# DSO_Front.net
KiCad netlist of a schematic drawn in Altium Designer
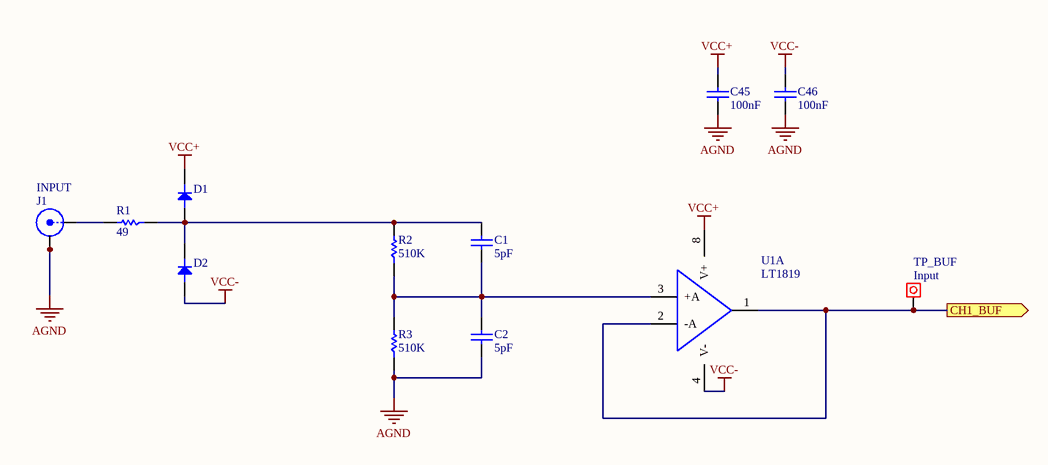
[diagram p0: DSO_Front.SchDoc]

(export (version "E")
  (design (tool "Eeschema 10.0.6"))
  (components
    (comp (ref "C1")
      (value "5pF")
      (footprint "0805C")
      (description "Capacitor")
      (fields (field (name "REVIEWED BY") "RM - 2018/08/05"))
      (libsource (lib "DSO") (part "C"))
    )
    (comp (ref "C2")
      (value "5pF")
      (footprint "0805C")
      (description "Capacitor")
      (fields (field (name "REVIEWED BY") "RM - 2018/08/05"))
      (libsource (lib "DSO") (part "C"))
    )
    (comp (ref "C45")
      (value "100nF")
      (footprint "0805C")
      (description "Capacitor")
      (fields (field (name "REVIEWED BY") "RM - 2018/08/05"))
      (libsource (lib "DSO") (part "C"))
    )
    (comp (ref "C46")
      (value "100nF")
      (footprint "0805C")
      (description "Capacitor")
      (fields (field (name "REVIEWED BY") "RM - 2018/08/05"))
      (libsource (lib "DSO") (part "C"))
    )
    (comp (ref "D1")
      (value "Diode")
      (footprint "SOD-123")
      (fields (field (name "REVIEWED BY") "RM - 2018/08/05"))
      (libsource (lib "DSO") (part "D"))
    )
    (comp (ref "D2")
      (value "Diode")
      (footprint "SOD-123")
      (fields (field (name "REVIEWED BY") "RM - 2018/08/05"))
      (libsource (lib "DSO") (part "D"))
    )
    (comp (ref "J1")
      (value "INPUT")
      (footprint "BNC_VERT")
      (description "BNC Straight")
      (fields (field (name "REVIEWED BY") "RM - 2018/08/05"))
      (libsource (lib "DSO") (part "BNC"))
    )
    (comp (ref "R1")
      (value "49")
      (footprint "0805")
      (description "Resistor")
      (fields (field (name "REVIEWED BY") "RM - 2018/08/05"))
      (libsource (lib "DSO") (part "R"))
    )
    (comp (ref "R2")
      (value "510K")
      (footprint "0805")
      (description "Resistor")
      (fields (field (name "REVIEWED BY") "RM - 2018/08/05"))
      (libsource (lib "DSO") (part "R"))
    )
    (comp (ref "R3")
      (value "510K")
      (footprint "0805")
      (description "Resistor")
      (fields (field (name "REVIEWED BY") "RM - 2018/08/05"))
      (libsource (lib "DSO") (part "R"))
    )
    (comp (ref "TP_BUF")
      (value "Input")
      (footprint "Testpoin")
      (description "Pad")
      (fields (field (name "Comment") "INPUT"))
      (libsource (lib "DSO") (part "Test Point"))
    )
    (comp (ref "U1")
      (value "LT1819")
      (footprint "SOIC-8")
      (description "OpAmp High Frequency Dual")
      (fields (field (name "REVIEWED BY") "RM - 2018/08/05"))
      (libsource (lib "DSO") (part "LT1819"))
    )
  )
  (nets
    (net (code "1") (name "/CH1_BUF") (class "Default")
      (node (ref "TP_BUF") (pin "1") (pintype "passive"))
      (node (ref "U1") (pin "1") (pinfunction "OUTA_1") (pintype "passive"))
      (node (ref "U1") (pin "2") (pinfunction "-A_2") (pintype "passive"))
    )
    (net (code "2") (name "AGND") (class "Default")
      (node (ref "C2") (pin "2") (pinfunction "2_2") (pintype "passive"))
      (node (ref "C45") (pin "2") (pinfunction "2_2") (pintype "passive"))
      (node (ref "C46") (pin "2") (pinfunction "2_2") (pintype "passive"))
      (node (ref "J1") (pin "2") (pinfunction "Y_2") (pintype "passive"))
      (node (ref "J1") (pin "3") (pinfunction "Y_3") (pintype "passive"))
      (node (ref "J1") (pin "4") (pinfunction "Y_4") (pintype "passive"))
      (node (ref "J1") (pin "5") (pinfunction "Y_5") (pintype "passive"))
      (node (ref "R3") (pin "1") (pintype "passive"))
    )
    (net (code "3") (name "Net-(C1-Pad1)") (class "Default")
      (node (ref "C1") (pin "1") (pinfunction "1_1") (pintype "passive"))
      (node (ref "D1") (pin "A") (pinfunction "A_A") (pintype "passive"))
      (node (ref "D2") (pin "K") (pinfunction "K_K") (pintype "passive"))
      (node (ref "R1") (pin "1") (pintype "passive"))
      (node (ref "R2") (pin "2") (pintype "passive"))
    )
    (net (code "4") (name "Net-(J1-X)") (class "Default")
      (node (ref "J1") (pin "1") (pinfunction "X_1") (pintype "passive"))
      (node (ref "R1") (pin "2") (pintype "passive"))
    )
    (net (code "5") (name "Net-(U1A-+A)") (class "Default")
      (node (ref "C1") (pin "2") (pinfunction "2_2") (pintype "passive"))
      (node (ref "C2") (pin "1") (pinfunction "1_1") (pintype "passive"))
      (node (ref "R2") (pin "1") (pintype "passive"))
      (node (ref "R3") (pin "2") (pintype "passive"))
      (node (ref "U1") (pin "3") (pinfunction "+A_3") (pintype "passive"))
    )
    (net (code "6") (name "VCC+") (class "Default")
      (node (ref "C45") (pin "1") (pinfunction "1_1") (pintype "passive"))
      (node (ref "D1") (pin "K") (pinfunction "K_K") (pintype "passive"))
      (node (ref "U1") (pin "8") (pinfunction "V+_8") (pintype "passive"))
    )
    (net (code "7") (name "VCC-") (class "Default")
      (node (ref "C46") (pin "1") (pinfunction "1_1") (pintype "passive"))
      (node (ref "D2") (pin "A") (pinfunction "A_A") (pintype "passive"))
      (node (ref "U1") (pin "4") (pinfunction "V-_4") (pintype "passive"))
    )
  )
)
